# Blinds_Driver.net
KiCad netlist of a schematic drawn in EAGLE
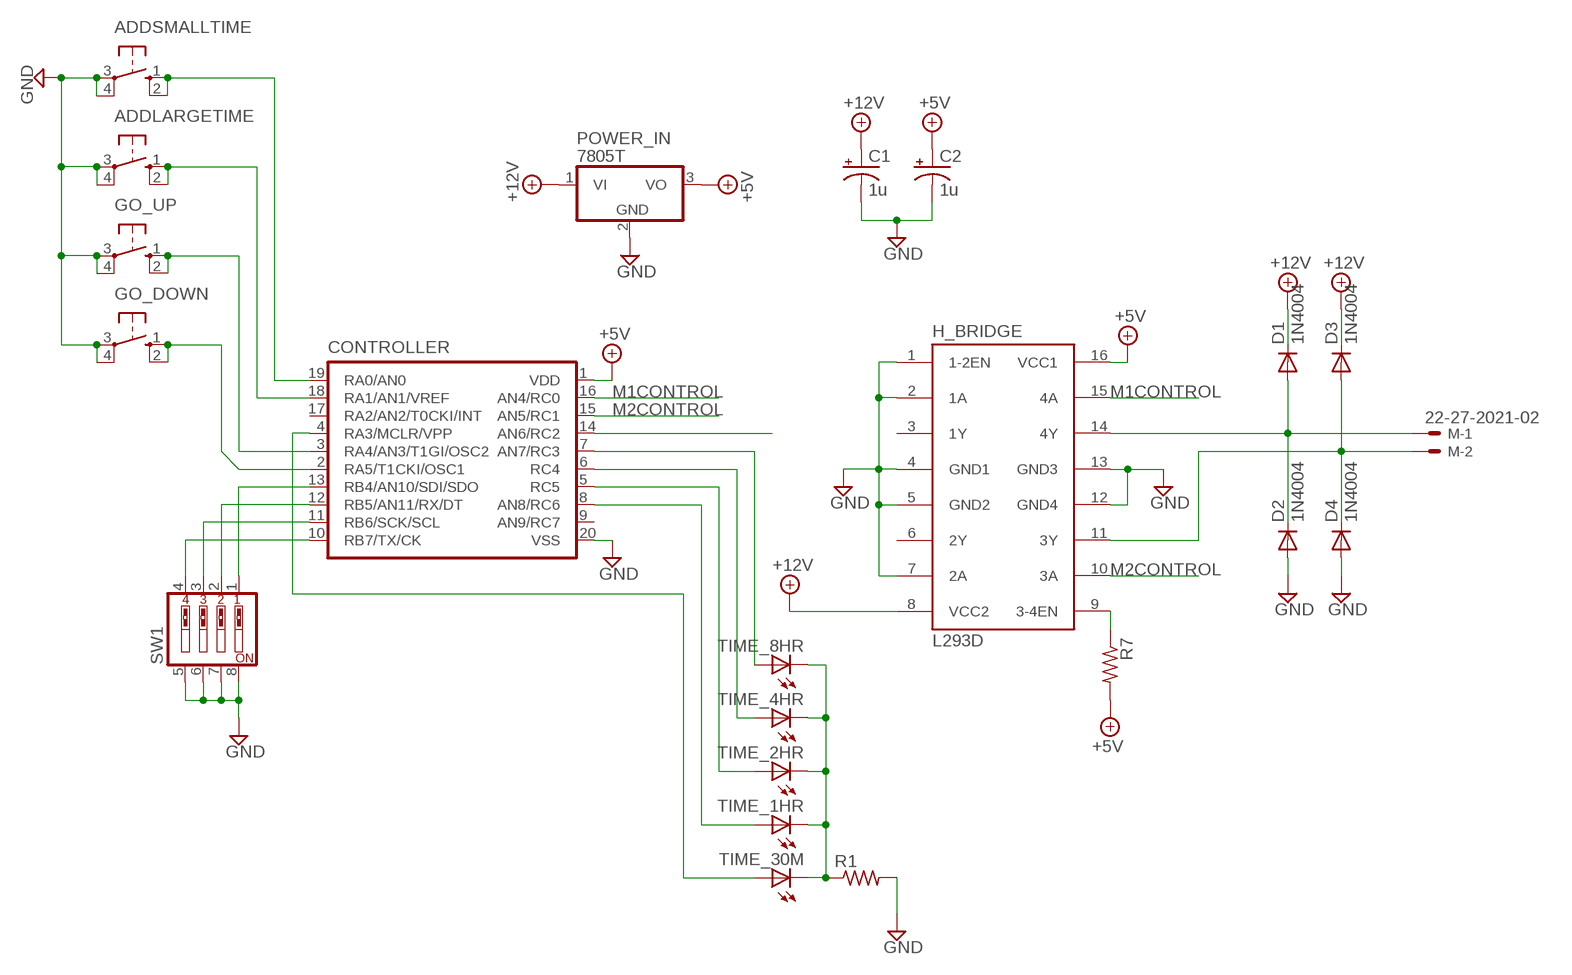
[diagram p0: schematic, sheet 1]

(export (version "E")
  (design (tool "Eeschema 10.0.6"))
  (components
    (comp (ref "ADDLARGETIME")
      (value "10-XX")
      (footprint "eagle-import:B3F-10XX")
      (fields (field (name "MPN") "B3F-1000"))
      (libsource (lib "eagle-import") (part "10-XX"))
    )
    (comp (ref "ADDSMALLTIME")
      (value "10-XX")
      (footprint "eagle-import:B3F-10XX")
      (fields (field (name "MPN") "B3F-1000"))
      (libsource (lib "eagle-import") (part "10-XX"))
    )
    (comp (ref "C1")
      (value "1u")
      (footprint "eagle-import:E2,5-6E")
      (libsource (lib "eagle-import") (part "CPOL-USE2,5-6E"))
    )
    (comp (ref "C2")
      (value "1u")
      (footprint "eagle-import:E2,5-6E")
      (libsource (lib "eagle-import") (part "CPOL-USE2,5-6E"))
    )
    (comp (ref "CONTROLLER")
      (value "PIC16F6XX")
      (footprint "eagle-import:DIL20")
      (libsource (lib "eagle-import") (part "PIC16F6XX"))
    )
    (comp (ref "D1")
      (value "1N4004")
      (footprint "eagle-import:DO41-10")
      (libsource (lib "eagle-import") (part "1N4004"))
    )
    (comp (ref "D2")
      (value "1N4004")
      (footprint "eagle-import:DO41-10")
      (libsource (lib "eagle-import") (part "1N4004"))
    )
    (comp (ref "D3")
      (value "1N4004")
      (footprint "eagle-import:DO41-10")
      (libsource (lib "eagle-import") (part "1N4004"))
    )
    (comp (ref "D4")
      (value "1N4004")
      (footprint "eagle-import:DO41-10")
      (libsource (lib "eagle-import") (part "1N4004"))
    )
    (comp (ref "GO_DOWN")
      (value "10-XX")
      (footprint "eagle-import:B3F-10XX")
      (fields (field (name "MPN") "B3F-1000"))
      (libsource (lib "eagle-import") (part "10-XX"))
    )
    (comp (ref "GO_UP")
      (value "10-XX")
      (footprint "eagle-import:B3F-10XX")
      (fields (field (name "MPN") "B3F-1000"))
      (libsource (lib "eagle-import") (part "10-XX"))
    )
    (comp (ref "H_BRIDGE")
      (value "L293D")
      (footprint "eagle-import:DIL16")
      (libsource (lib "eagle-import") (part "L293D"))
    )
    (comp (ref "M")
      (value "22-27-2021-02")
      (footprint "eagle-import:6410-02")
      (libsource (lib "eagle-import") (part "22-?-0227-2021"))
    )
    (comp (ref "POWER_IN")
      (value "7805T")
      (footprint "eagle-import:TO220H")
      (libsource (lib "eagle-import") (part "78T05"))
    )
    (comp (ref "R1")
      (value "R-US_0207/10")
      (footprint "eagle-import:0207_10")
      (libsource (lib "eagle-import") (part "R-US_0207/10"))
    )
    (comp (ref "R7")
      (value "R-US_0207/10")
      (footprint "eagle-import:0207_10")
      (libsource (lib "eagle-import") (part "R-US_0207/10"))
    )
    (comp (ref "SW1")
      (value "SW_DIP-4")
      (footprint "eagle-import:EDG-04")
      (libsource (lib "eagle-import") (part "SW_DIP-4"))
    )
    (comp (ref "TIME_1HR")
      (value "LED5MM")
      (footprint "eagle-import:LED5MM")
      (libsource (lib "eagle-import") (part "LED5MM"))
    )
    (comp (ref "TIME_2HR")
      (value "LED5MM")
      (footprint "eagle-import:LED5MM")
      (libsource (lib "eagle-import") (part "LED5MM"))
    )
    (comp (ref "TIME_4HR")
      (value "LED5MM")
      (footprint "eagle-import:LED5MM")
      (libsource (lib "eagle-import") (part "LED5MM"))
    )
    (comp (ref "TIME_8HR")
      (value "LED5MM")
      (footprint "eagle-import:LED5MM")
      (libsource (lib "eagle-import") (part "LED5MM"))
    )
    (comp (ref "TIME_30M")
      (value "LED5MM")
      (footprint "eagle-import:LED5MM")
      (libsource (lib "eagle-import") (part "LED5MM"))
    )
  )
  (nets
    (net (code "1") (name "+5V") (class "Default")
      (node (ref "C2") (pin "+") (pinfunction "+_+") (pintype "passive"))
      (node (ref "CONTROLLER") (pin "1") (pinfunction "VDD_1") (pintype "power_in"))
      (node (ref "H_BRIDGE") (pin "16") (pinfunction "VCC1_16") (pintype "power_in"))
      (node (ref "POWER_IN") (pin "3") (pinfunction "VO_3") (pintype "passive"))
      (node (ref "R7") (pin "2") (pinfunction "2_2") (pintype "passive"))
    )
    (net (code "2") (name "+12V") (class "Default")
      (node (ref "C1") (pin "+") (pinfunction "+_+") (pintype "passive"))
      (node (ref "D1") (pin "C") (pinfunction "C_C") (pintype "passive"))
      (node (ref "D3") (pin "C") (pinfunction "C_C") (pintype "passive"))
      (node (ref "H_BRIDGE") (pin "8") (pinfunction "VCC2_8") (pintype "power_in"))
      (node (ref "POWER_IN") (pin "1") (pinfunction "VI_1") (pintype "input"))
    )
    (net (code "3") (name "/M1CONTROL") (class "Default")
      (node (ref "CONTROLLER") (pin "16") (pinfunction "AN4/RC0_16") (pintype "bidirectional"))
      (node (ref "H_BRIDGE") (pin "15") (pinfunction "4A_15") (pintype "input"))
    )
    (net (code "4") (name "/M2CONTROL") (class "Default")
      (node (ref "CONTROLLER") (pin "15") (pinfunction "AN5/RC1_15") (pintype "bidirectional"))
      (node (ref "H_BRIDGE") (pin "10") (pinfunction "3A_10") (pintype "input"))
    )
    (net (code "5") (name "GND") (class "Default")
      (node (ref "ADDLARGETIME") (pin "3") (pinfunction "P_3") (pintype "passive"))
      (node (ref "ADDLARGETIME") (pin "4") (pinfunction "P1_4") (pintype "passive"))
      (node (ref "ADDSMALLTIME") (pin "3") (pinfunction "P_3") (pintype "passive"))
      (node (ref "ADDSMALLTIME") (pin "4") (pinfunction "P1_4") (pintype "passive"))
      (node (ref "C1") (pin "-") (pinfunction "-_-") (pintype "passive"))
      (node (ref "C2") (pin "-") (pinfunction "-_-") (pintype "passive"))
      (node (ref "CONTROLLER") (pin "20") (pinfunction "VSS_20") (pintype "power_in"))
      (node (ref "D2") (pin "A") (pinfunction "A_A") (pintype "passive"))
      (node (ref "D4") (pin "A") (pinfunction "A_A") (pintype "passive"))
      (node (ref "GO_DOWN") (pin "3") (pinfunction "P_3") (pintype "passive"))
      (node (ref "GO_DOWN") (pin "4") (pinfunction "P1_4") (pintype "passive"))
      (node (ref "GO_UP") (pin "3") (pinfunction "P_3") (pintype "passive"))
      (node (ref "GO_UP") (pin "4") (pinfunction "P1_4") (pintype "passive"))
      (node (ref "H_BRIDGE") (pin "1") (pinfunction "1-2EN_1") (pintype "input"))
      (node (ref "H_BRIDGE") (pin "12") (pinfunction "GND4_12") (pintype "power_in"))
      (node (ref "H_BRIDGE") (pin "13") (pinfunction "GND3_13") (pintype "power_in"))
      (node (ref "H_BRIDGE") (pin "2") (pinfunction "1A_2") (pintype "input"))
      (node (ref "H_BRIDGE") (pin "4") (pinfunction "GND1_4") (pintype "power_in"))
      (node (ref "H_BRIDGE") (pin "5") (pinfunction "GND2_5") (pintype "power_in"))
      (node (ref "H_BRIDGE") (pin "7") (pinfunction "2A_7") (pintype "input"))
      (node (ref "POWER_IN") (pin "2") (pinfunction "GND_2") (pintype "passive"))
      (node (ref "R1") (pin "2") (pinfunction "2_2") (pintype "passive"))
      (node (ref "SW1") (pin "5") (pinfunction "5_5") (pintype "passive"))
      (node (ref "SW1") (pin "6") (pinfunction "6_6") (pintype "passive"))
      (node (ref "SW1") (pin "7") (pinfunction "7_7") (pintype "passive"))
      (node (ref "SW1") (pin "8") (pinfunction "8_8") (pintype "passive"))
    )
    (net (code "6") (name "Net-(ADDLARGETIME-S)") (class "Default")
      (node (ref "ADDLARGETIME") (pin "1") (pinfunction "S_1") (pintype "passive"))
      (node (ref "ADDLARGETIME") (pin "2") (pinfunction "S1_2") (pintype "passive"))
      (node (ref "CONTROLLER") (pin "18") (pinfunction "RA1/AN1/VREF_18") (pintype "bidirectional"))
    )
    (net (code "7") (name "Net-(ADDSMALLTIME-S)") (class "Default")
      (node (ref "ADDSMALLTIME") (pin "1") (pinfunction "S_1") (pintype "passive"))
      (node (ref "ADDSMALLTIME") (pin "2") (pinfunction "S1_2") (pintype "passive"))
      (node (ref "CONTROLLER") (pin "19") (pinfunction "RA0/AN0_19") (pintype "bidirectional"))
    )
    (net (code "8") (name "Net-(CONTROLLER-AN7{slash}RC3)") (class "Default")
      (node (ref "CONTROLLER") (pin "7") (pinfunction "AN7/RC3_7") (pintype "bidirectional"))
      (node (ref "TIME_8HR") (pin "A") (pinfunction "A_A") (pintype "passive"))
    )
    (net (code "9") (name "Net-(CONTROLLER-AN8{slash}RC6)") (class "Default")
      (node (ref "CONTROLLER") (pin "8") (pinfunction "AN8/RC6_8") (pintype "bidirectional"))
      (node (ref "TIME_1HR") (pin "A") (pinfunction "A_A") (pintype "passive"))
    )
    (net (code "10") (name "Net-(CONTROLLER-RA3{slash}MCLR{slash}VPP)") (class "Default")
      (node (ref "CONTROLLER") (pin "4") (pinfunction "RA3/MCLR/VPP_4") (pintype "input"))
      (node (ref "TIME_30M") (pin "A") (pinfunction "A_A") (pintype "passive"))
    )
    (net (code "11") (name "Net-(CONTROLLER-RA4{slash}AN3{slash}T1GI{slash}OSC2)") (class "Default")
      (node (ref "CONTROLLER") (pin "3") (pinfunction "RA4/AN3/T1GI/OSC2_3") (pintype "bidirectional"))
      (node (ref "GO_UP") (pin "1") (pinfunction "S_1") (pintype "passive"))
      (node (ref "GO_UP") (pin "2") (pinfunction "S1_2") (pintype "passive"))
    )
    (net (code "12") (name "Net-(CONTROLLER-RA5{slash}T1CKI{slash}OSC1)") (class "Default")
      (node (ref "CONTROLLER") (pin "2") (pinfunction "RA5/T1CKI/OSC1_2") (pintype "bidirectional"))
      (node (ref "GO_DOWN") (pin "1") (pinfunction "S_1") (pintype "passive"))
      (node (ref "GO_DOWN") (pin "2") (pinfunction "S1_2") (pintype "passive"))
    )
    (net (code "13") (name "Net-(CONTROLLER-RB4{slash}AN10{slash}SDI{slash}SDO)") (class "Default")
      (node (ref "CONTROLLER") (pin "13") (pinfunction "RB4/AN10/SDI/SDO_13") (pintype "bidirectional"))
      (node (ref "SW1") (pin "1") (pinfunction "1_1") (pintype "passive"))
    )
    (net (code "14") (name "Net-(CONTROLLER-RB5{slash}AN11{slash}RX{slash}DT)") (class "Default")
      (node (ref "CONTROLLER") (pin "12") (pinfunction "RB5/AN11/RX/DT_12") (pintype "bidirectional"))
      (node (ref "SW1") (pin "2") (pinfunction "2_2") (pintype "passive"))
    )
    (net (code "15") (name "Net-(CONTROLLER-RB6{slash}SCK{slash}SCL)") (class "Default")
      (node (ref "CONTROLLER") (pin "11") (pinfunction "RB6/SCK/SCL_11") (pintype "bidirectional"))
      (node (ref "SW1") (pin "3") (pinfunction "3_3") (pintype "passive"))
    )
    (net (code "16") (name "Net-(CONTROLLER-RB7{slash}TX{slash}CK)") (class "Default")
      (node (ref "CONTROLLER") (pin "10") (pinfunction "RB7/TX/CK_10") (pintype "bidirectional"))
      (node (ref "SW1") (pin "4") (pinfunction "4_4") (pintype "passive"))
    )
    (net (code "17") (name "Net-(CONTROLLER-RC4)") (class "Default")
      (node (ref "CONTROLLER") (pin "6") (pinfunction "RC4_6") (pintype "bidirectional"))
      (node (ref "TIME_4HR") (pin "A") (pinfunction "A_A") (pintype "passive"))
    )
    (net (code "18") (name "Net-(CONTROLLER-RC5)") (class "Default")
      (node (ref "CONTROLLER") (pin "5") (pinfunction "RC5_5") (pintype "bidirectional"))
      (node (ref "TIME_2HR") (pin "A") (pinfunction "A_A") (pintype "passive"))
    )
    (net (code "19") (name "Net-(H_BRIDGE-3-4EN)") (class "Default")
      (node (ref "H_BRIDGE") (pin "9") (pinfunction "3-4EN_9") (pintype "input"))
      (node (ref "R7") (pin "1") (pinfunction "1_1") (pintype "passive"))
    )
    (net (code "20") (name "Net-(H_BRIDGE-3Y)") (class "Default")
      (node (ref "D3") (pin "A") (pinfunction "A_A") (pintype "passive"))
      (node (ref "D4") (pin "C") (pinfunction "C_C") (pintype "passive"))
      (node (ref "H_BRIDGE") (pin "11") (pinfunction "3Y_11") (pintype "output"))
      (node (ref "M") (pin "2") (pinfunction "S_2") (pintype "passive"))
    )
    (net (code "21") (name "Net-(H_BRIDGE-4Y)") (class "Default")
      (node (ref "D1") (pin "A") (pinfunction "A_A") (pintype "passive"))
      (node (ref "D2") (pin "C") (pinfunction "C_C") (pintype "passive"))
      (node (ref "H_BRIDGE") (pin "14") (pinfunction "4Y_14") (pintype "output"))
      (node (ref "M") (pin "1") (pinfunction "S_1") (pintype "passive"))
    )
    (net (code "22") (name "Net-(TIME_1HR-C)") (class "Default")
      (node (ref "R1") (pin "1") (pinfunction "1_1") (pintype "passive"))
      (node (ref "TIME_1HR") (pin "K") (pinfunction "C_K") (pintype "passive"))
      (node (ref "TIME_2HR") (pin "K") (pinfunction "C_K") (pintype "passive"))
      (node (ref "TIME_30M") (pin "K") (pinfunction "C_K") (pintype "passive"))
      (node (ref "TIME_4HR") (pin "K") (pinfunction "C_K") (pintype "passive"))
      (node (ref "TIME_8HR") (pin "K") (pinfunction "C_K") (pintype "passive"))
    )
    (net (code "23") (name "unconnected-(CONTROLLER-AN6{slash}RC2-Pad14)") (class "Default")
      (node (ref "CONTROLLER") (pin "14") (pinfunction "AN6/RC2_14") (pintype "bidirectional"))
    )
    (net (code "24") (name "unconnected-(CONTROLLER-AN9{slash}RC7-Pad9)") (class "Default")
      (node (ref "CONTROLLER") (pin "9") (pinfunction "AN9/RC7_9") (pintype "bidirectional"))
    )
    (net (code "25") (name "unconnected-(CONTROLLER-RA2{slash}AN2{slash}T0CKI{slash}INT-Pad17)") (class "Default")
      (node (ref "CONTROLLER") (pin "17") (pinfunction "RA2/AN2/T0CKI/INT_17") (pintype "bidirectional"))
    )
    (net (code "26") (name "unconnected-(H_BRIDGE-1Y-Pad3)") (class "Default")
      (node (ref "H_BRIDGE") (pin "3") (pinfunction "1Y_3") (pintype "output"))
    )
    (net (code "27") (name "unconnected-(H_BRIDGE-2Y-Pad6)") (class "Default")
      (node (ref "H_BRIDGE") (pin "6") (pinfunction "2Y_6") (pintype "output"))
    )
  )
)
